# BME280_Breakout.net
KiCad netlist of a schematic drawn in EAGLE
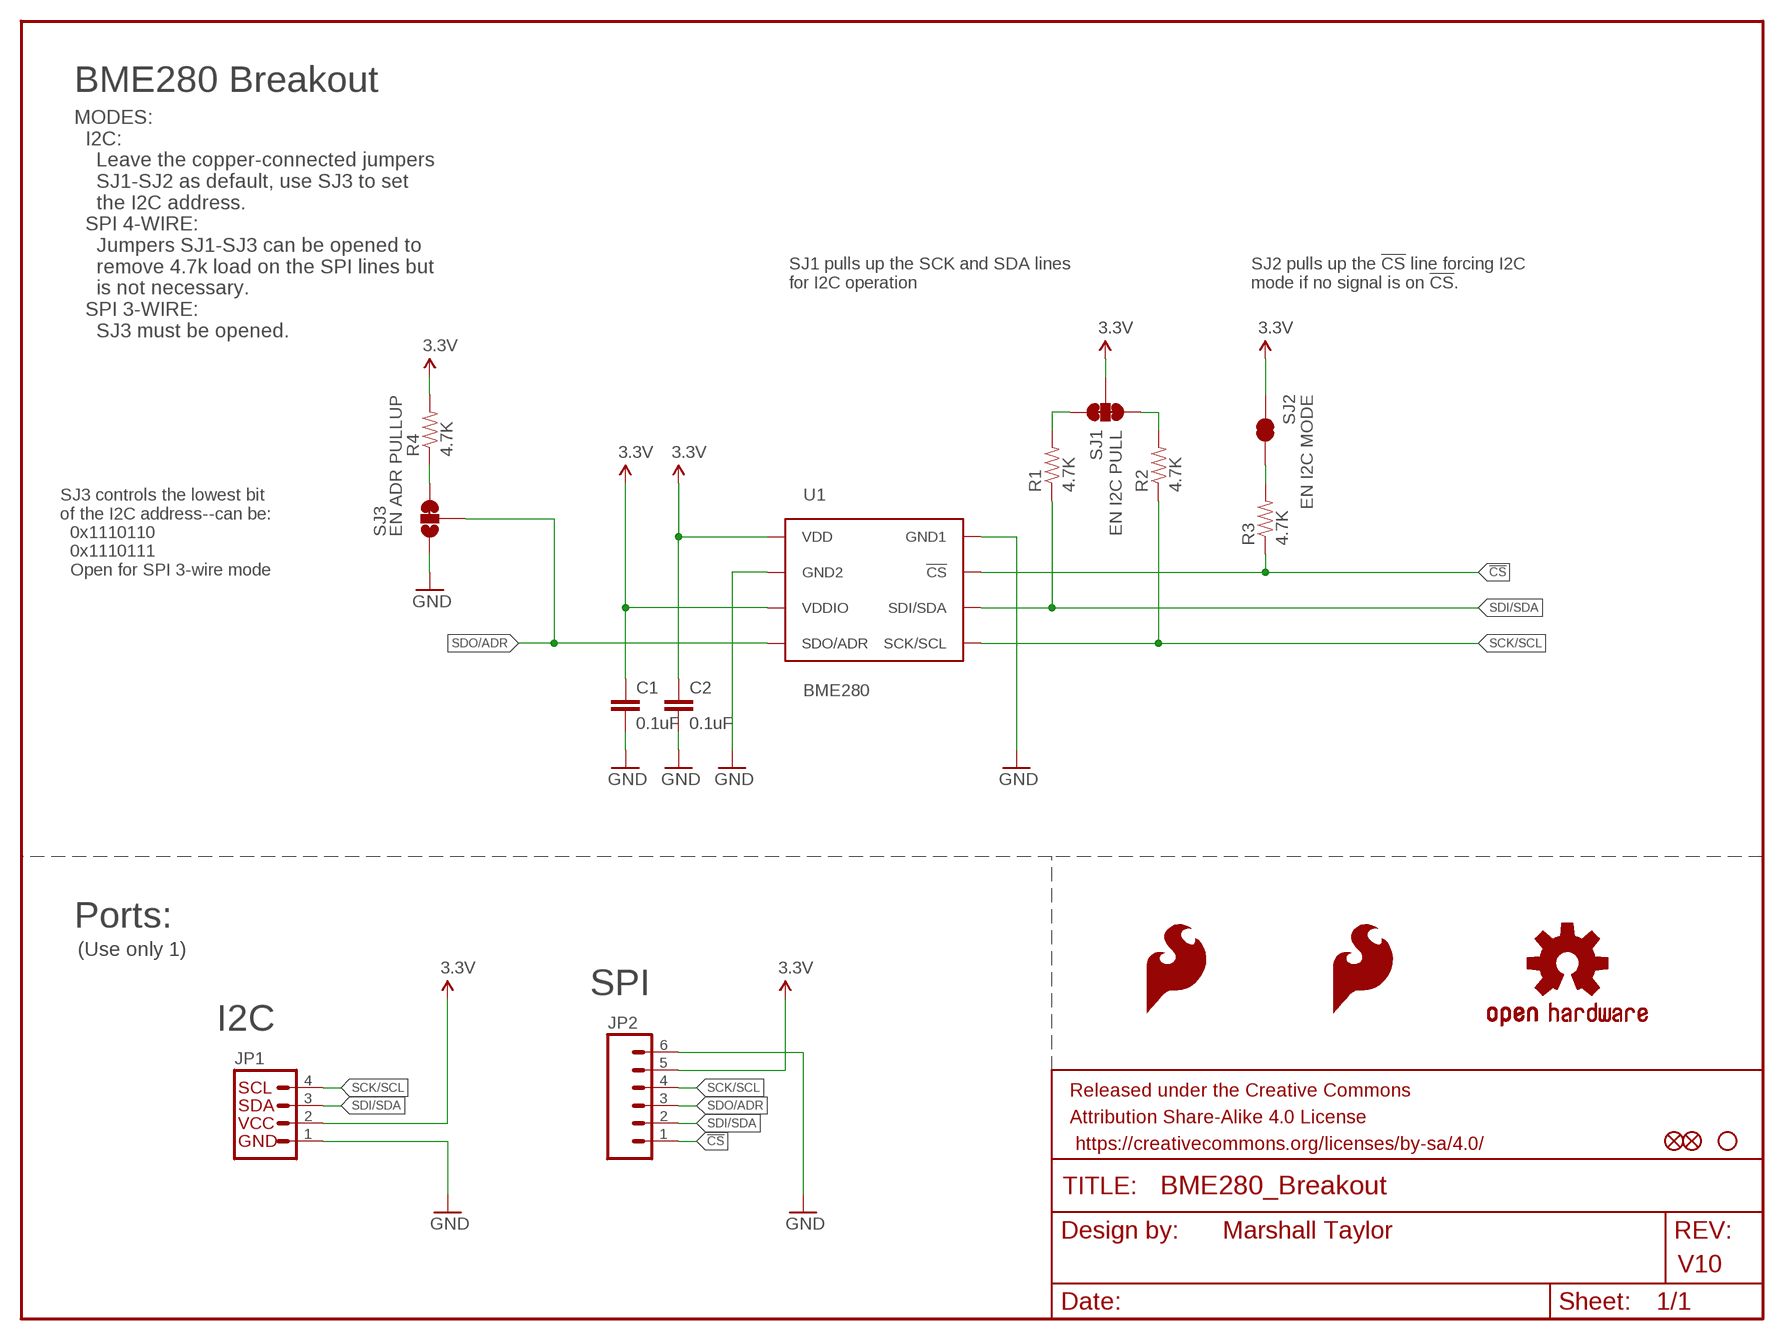
[diagram p0: schematic, sheet 1]

(export (version "E")
  (design (tool "Eeschema 10.0.6"))
  (components
    (comp (ref "C1")
      (value "0.1uF")
      (footprint "eagle-import:0603-CAP")
      (libsource (lib "eagle-import") (part "0.1UF-25V-5%(0603)"))
    )
    (comp (ref "C2")
      (value "0.1uF")
      (footprint "eagle-import:0603-CAP")
      (libsource (lib "eagle-import") (part "0.1UF-25V-5%(0603)"))
    )
    (comp (ref "FID1")
      (value "FIDUCIAL1X2")
      (footprint "eagle-import:FIDUCIAL-1X2")
      (libsource (lib "eagle-import") (part "FIDUCIAL1X2"))
    )
    (comp (ref "FID2")
      (value "FIDUCIAL1X2")
      (footprint "eagle-import:FIDUCIAL-1X2")
      (libsource (lib "eagle-import") (part "FIDUCIAL1X2"))
    )
    (comp (ref "FRAME1")
      (value "FRAME-LETTER")
      (footprint "eagle-import:CREATIVE_COMMONS")
      (libsource (lib "eagle-import") (part "FRAME-LETTER"))
    )
    (comp (ref "JP1")
      (value "I2C_STANDARD_NO_SILK")
      (footprint "eagle-import:1X04_NO_SILK")
      (libsource (lib "eagle-import") (part "I2C_STANDARD_NO_SILK"))
    )
    (comp (ref "JP2")
      (value "M06NO_SILK_FEMALE_PTH")
      (footprint "eagle-import:1X06_NO_SILK")
      (libsource (lib "eagle-import") (part "M06NO_SILK_FEMALE_PTH"))
    )
    (comp (ref "LOGO1")
      (value "SFE_LOGO_FLAME.1_INCH")
      (footprint "eagle-import:SFE_LOGO_FLAME_.1")
      (libsource (lib "eagle-import") (part "SFE_LOGO_FLAME.1_INCH"))
    )
    (comp (ref "LOGO2")
      (value "SFE_LOGO_FLAME.1_INCH")
      (footprint "eagle-import:SFE_LOGO_FLAME_.1")
      (libsource (lib "eagle-import") (part "SFE_LOGO_FLAME.1_INCH"))
    )
    (comp (ref "LOGO3")
      (value "OSHW-LOGOS")
      (footprint "eagle-import:OSHW-LOGO-S")
      (libsource (lib "eagle-import") (part "OSHW-LOGOS"))
    )
    (comp (ref "R1")
      (value "4.7K")
      (footprint "eagle-import:0603-RES")
      (libsource (lib "eagle-import") (part "4.7KOHM-1/10W-1%(0603)"))
    )
    (comp (ref "R2")
      (value "4.7K")
      (footprint "eagle-import:0603-RES")
      (libsource (lib "eagle-import") (part "4.7KOHM-1/10W-1%(0603)"))
    )
    (comp (ref "R3")
      (value "4.7K")
      (footprint "eagle-import:0603-RES")
      (libsource (lib "eagle-import") (part "4.7KOHM-1/10W-1%(0603)"))
    )
    (comp (ref "R4")
      (value "4.7K")
      (footprint "eagle-import:0603-RES")
      (libsource (lib "eagle-import") (part "4.7KOHM-1/10W-1%(0603)"))
    )
    (comp (ref "SJ1")
      (value "EN I2C PULL")
      (footprint "eagle-import:PAD-JUMPER-3-3OF3_NC_BY_TRACE_YES_SILK_FULL_BOX")
      (libsource (lib "eagle-import") (part "JUMPER-PAD-3-NC_BY_TRACE"))
    )
    (comp (ref "SJ2")
      (value "EN I2C MODE")
      (footprint "eagle-import:PAD-JUMPER-2-NC_BY_TRACE_YES_SILK")
      (libsource (lib "eagle-import") (part "JUMPER-PAD-2-NC_BY_TRACE"))
    )
    (comp (ref "SJ3")
      (value "EN ADR PULLUP")
      (footprint "eagle-import:PAD-JUMPER-3-2OF3_NC_BY_TRACE_YES_SILK_FULL_BOX")
      (libsource (lib "eagle-import") (part "JUMPER-PAD-3-2OF3_NC_BY_TRACE_SMALL"))
    )
    (comp (ref "STANDOFF4")
      (value "STAND-OFF")
      (footprint "eagle-import:STAND-OFF")
      (libsource (lib "eagle-import") (part "STAND-OFF"))
    )
    (comp (ref "U1")
      (value "BME280")
      (footprint "eagle-import:BME280_LGA")
      (libsource (lib "eagle-import") (part "BME280"))
    )
  )
  (nets
    (net (code "1") (name "/~{CS}") (class "Default")
      (node (ref "JP2") (pin "1") (pinfunction "1_1") (pintype "passive"))
      (node (ref "R3") (pin "1") (pinfunction "1_1") (pintype "passive"))
      (node (ref "U1") (pin "P$2") (pinfunction "~{CS}_P$2") (pintype "bidirectional"))
    )
    (net (code "2") (name "3.3V") (class "Default")
      (node (ref "C1") (pin "1") (pinfunction "1_1") (pintype "passive"))
      (node (ref "C2") (pin "1") (pinfunction "1_1") (pintype "passive"))
      (node (ref "JP1") (pin "2") (pinfunction "2_2") (pintype "passive"))
      (node (ref "JP2") (pin "5") (pinfunction "5_5") (pintype "passive"))
      (node (ref "R4") (pin "2") (pinfunction "2_2") (pintype "passive"))
      (node (ref "SJ1") (pin "2") (pinfunction "2_2") (pintype "passive"))
      (node (ref "SJ2") (pin "2") (pinfunction "2_2") (pintype "passive"))
      (node (ref "U1") (pin "P$6") (pinfunction "VDDIO_P$6") (pintype "bidirectional"))
      (node (ref "U1") (pin "P$8") (pinfunction "VDD_P$8") (pintype "bidirectional"))
    )
    (net (code "3") (name "GND") (class "Default")
      (node (ref "C1") (pin "2") (pinfunction "2_2") (pintype "passive"))
      (node (ref "C2") (pin "2") (pinfunction "2_2") (pintype "passive"))
      (node (ref "JP1") (pin "1") (pinfunction "1_1") (pintype "passive"))
      (node (ref "JP2") (pin "6") (pinfunction "6_6") (pintype "passive"))
      (node (ref "SJ3") (pin "1") (pinfunction "1_1") (pintype "passive"))
      (node (ref "U1") (pin "P$1") (pinfunction "GND1_P$1") (pintype "bidirectional"))
      (node (ref "U1") (pin "P$7") (pinfunction "GND2_P$7") (pintype "bidirectional"))
    )
    (net (code "4") (name "Net-(R1-Pad2)") (class "Default")
      (node (ref "R1") (pin "2") (pinfunction "2_2") (pintype "passive"))
      (node (ref "SJ1") (pin "3") (pinfunction "3_3") (pintype "passive"))
    )
    (net (code "5") (name "Net-(R2-Pad2)") (class "Default")
      (node (ref "R2") (pin "2") (pinfunction "2_2") (pintype "passive"))
      (node (ref "SJ1") (pin "1") (pinfunction "1_1") (pintype "passive"))
    )
    (net (code "6") (name "Net-(R3-Pad2)") (class "Default")
      (node (ref "R3") (pin "2") (pinfunction "2_2") (pintype "passive"))
      (node (ref "SJ2") (pin "1") (pinfunction "1_1") (pintype "passive"))
    )
    (net (code "7") (name "Net-(R4-Pad1)") (class "Default")
      (node (ref "R4") (pin "1") (pinfunction "1_1") (pintype "passive"))
      (node (ref "SJ3") (pin "3") (pinfunction "3_3") (pintype "passive"))
    )
    (net (code "8") (name "SCK{slash}SCL") (class "Default")
      (node (ref "JP1") (pin "4") (pinfunction "4_4") (pintype "passive"))
      (node (ref "JP2") (pin "4") (pinfunction "4_4") (pintype "passive"))
      (node (ref "R2") (pin "1") (pinfunction "1_1") (pintype "passive"))
      (node (ref "U1") (pin "P$4") (pinfunction "SCK/SCL_P$4") (pintype "bidirectional"))
    )
    (net (code "9") (name "SDI{slash}SDA") (class "Default")
      (node (ref "JP1") (pin "3") (pinfunction "3_3") (pintype "passive"))
      (node (ref "JP2") (pin "2") (pinfunction "2_2") (pintype "passive"))
      (node (ref "R1") (pin "1") (pinfunction "1_1") (pintype "passive"))
      (node (ref "U1") (pin "P$3") (pinfunction "SDI/SDA_P$3") (pintype "bidirectional"))
    )
    (net (code "10") (name "SDO{slash}ADR") (class "Default")
      (node (ref "JP2") (pin "3") (pinfunction "3_3") (pintype "passive"))
      (node (ref "SJ3") (pin "2") (pinfunction "2_2") (pintype "passive"))
      (node (ref "U1") (pin "P$5") (pinfunction "SDO/ADR_P$5") (pintype "bidirectional"))
    )
  )
)
